# Role_Unit.net
KiCad netlist of a schematic drawn in Altium Designer
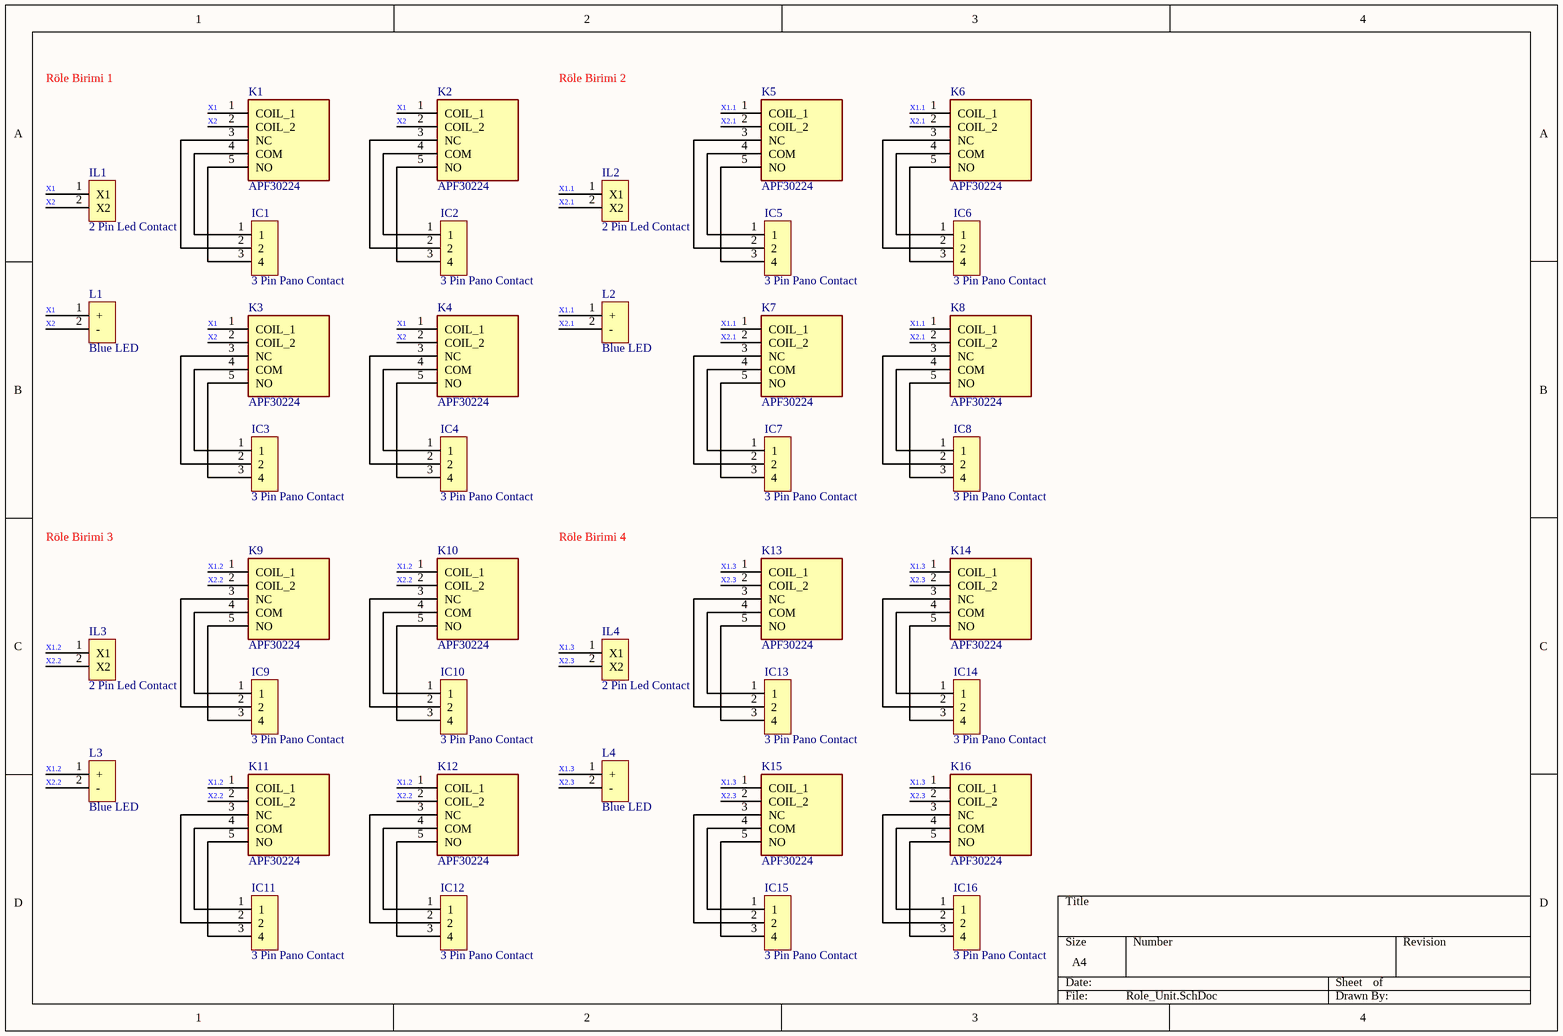
[diagram p0: Role_Unit.SchDoc]

(export (version "E")
  (design (tool "Eeschema 10.0.6"))
  (components
    (comp (ref "IC1")
      (value "3 Pin Pano Contact")
      (footprint "Contact")
      (libsource (lib "STANDART KUMANDA PANELİ") (part "Contact"))
    )
    (comp (ref "IC2")
      (value "3 Pin Pano Contact")
      (footprint "Contact")
      (libsource (lib "STANDART KUMANDA PANELİ") (part "Contact"))
    )
    (comp (ref "IC3")
      (value "3 Pin Pano Contact")
      (footprint "Contact")
      (libsource (lib "STANDART KUMANDA PANELİ") (part "Contact"))
    )
    (comp (ref "IC4")
      (value "3 Pin Pano Contact")
      (footprint "Contact")
      (libsource (lib "STANDART KUMANDA PANELİ") (part "Contact"))
    )
    (comp (ref "IC5")
      (value "3 Pin Pano Contact")
      (footprint "Contact")
      (libsource (lib "STANDART KUMANDA PANELİ") (part "Contact"))
    )
    (comp (ref "IC6")
      (value "3 Pin Pano Contact")
      (footprint "Contact")
      (libsource (lib "STANDART KUMANDA PANELİ") (part "Contact"))
    )
    (comp (ref "IC7")
      (value "3 Pin Pano Contact")
      (footprint "Contact")
      (libsource (lib "STANDART KUMANDA PANELİ") (part "Contact"))
    )
    (comp (ref "IC8")
      (value "3 Pin Pano Contact")
      (footprint "Contact")
      (libsource (lib "STANDART KUMANDA PANELİ") (part "Contact"))
    )
    (comp (ref "IC9")
      (value "3 Pin Pano Contact")
      (footprint "Contact")
      (libsource (lib "STANDART KUMANDA PANELİ") (part "Contact"))
    )
    (comp (ref "IC10")
      (value "3 Pin Pano Contact")
      (footprint "Contact")
      (libsource (lib "STANDART KUMANDA PANELİ") (part "Contact"))
    )
    (comp (ref "IC11")
      (value "3 Pin Pano Contact")
      (footprint "Contact")
      (libsource (lib "STANDART KUMANDA PANELİ") (part "Contact"))
    )
    (comp (ref "IC12")
      (value "3 Pin Pano Contact")
      (footprint "Contact")
      (libsource (lib "STANDART KUMANDA PANELİ") (part "Contact"))
    )
    (comp (ref "IC13")
      (value "3 Pin Pano Contact")
      (footprint "Contact")
      (libsource (lib "STANDART KUMANDA PANELİ") (part "Contact"))
    )
    (comp (ref "IC14")
      (value "3 Pin Pano Contact")
      (footprint "Contact")
      (libsource (lib "STANDART KUMANDA PANELİ") (part "Contact"))
    )
    (comp (ref "IC15")
      (value "3 Pin Pano Contact")
      (footprint "Contact")
      (libsource (lib "STANDART KUMANDA PANELİ") (part "Contact"))
    )
    (comp (ref "IC16")
      (value "3 Pin Pano Contact")
      (footprint "Contact")
      (libsource (lib "STANDART KUMANDA PANELİ") (part "Contact"))
    )
    (comp (ref "IL1")
      (value "2 Pin Led Contact")
      (footprint "Standart Kumanda Paneli:LED_Contact")
      (libsource (lib "STANDART KUMANDA PANELİ") (part "LED_Contact"))
    )
    (comp (ref "IL2")
      (value "2 Pin Led Contact")
      (footprint "Standart Kumanda Paneli:LED_Contact")
      (libsource (lib "STANDART KUMANDA PANELİ") (part "LED_Contact"))
    )
    (comp (ref "IL3")
      (value "2 Pin Led Contact")
      (footprint "Standart Kumanda Paneli:LED_Contact")
      (libsource (lib "STANDART KUMANDA PANELİ") (part "LED_Contact"))
    )
    (comp (ref "IL4")
      (value "2 Pin Led Contact")
      (footprint "Standart Kumanda Paneli:LED_Contact")
      (libsource (lib "STANDART KUMANDA PANELİ") (part "LED_Contact"))
    )
    (comp (ref "K1")
      (value "APF30224")
      (footprint "SamacSys:APF30224")
      (description "Relay or Contactor")
      (fields (field (name "MOUSER PART NUMBER") "769-APF30224"))
      (libsource (lib "STANDART KUMANDA PANELİ") (part "APF30224"))
    )
    (comp (ref "K2")
      (value "APF30224")
      (footprint "SamacSys:APF30224")
      (description "Relay or Contactor")
      (fields (field (name "MOUSER PART NUMBER") "769-APF30224"))
      (libsource (lib "STANDART KUMANDA PANELİ") (part "APF30224"))
    )
    (comp (ref "K3")
      (value "APF30224")
      (footprint "SamacSys:APF30224")
      (description "Relay or Contactor")
      (fields (field (name "MOUSER PART NUMBER") "769-APF30224"))
      (libsource (lib "STANDART KUMANDA PANELİ") (part "APF30224"))
    )
    (comp (ref "K4")
      (value "APF30224")
      (footprint "SamacSys:APF30224")
      (description "Relay or Contactor")
      (fields (field (name "MOUSER PART NUMBER") "769-APF30224"))
      (libsource (lib "STANDART KUMANDA PANELİ") (part "APF30224"))
    )
    (comp (ref "K5")
      (value "APF30224")
      (footprint "SamacSys:APF30224")
      (description "Relay or Contactor")
      (fields (field (name "MOUSER PART NUMBER") "769-APF30224"))
      (libsource (lib "STANDART KUMANDA PANELİ") (part "APF30224"))
    )
    (comp (ref "K6")
      (value "APF30224")
      (footprint "SamacSys:APF30224")
      (description "Relay or Contactor")
      (fields (field (name "MOUSER PART NUMBER") "769-APF30224"))
      (libsource (lib "STANDART KUMANDA PANELİ") (part "APF30224"))
    )
    (comp (ref "K7")
      (value "APF30224")
      (footprint "SamacSys:APF30224")
      (description "Relay or Contactor")
      (fields (field (name "MOUSER PART NUMBER") "769-APF30224"))
      (libsource (lib "STANDART KUMANDA PANELİ") (part "APF30224"))
    )
    (comp (ref "K8")
      (value "APF30224")
      (footprint "SamacSys:APF30224")
      (description "Relay or Contactor")
      (fields (field (name "MOUSER PART NUMBER") "769-APF30224"))
      (libsource (lib "STANDART KUMANDA PANELİ") (part "APF30224"))
    )
    (comp (ref "K9")
      (value "APF30224")
      (footprint "SamacSys:APF30224")
      (description "Relay or Contactor")
      (fields (field (name "MOUSER PART NUMBER") "769-APF30224"))
      (libsource (lib "STANDART KUMANDA PANELİ") (part "APF30224"))
    )
    (comp (ref "K10")
      (value "APF30224")
      (footprint "SamacSys:APF30224")
      (description "Relay or Contactor")
      (fields (field (name "MOUSER PART NUMBER") "769-APF30224"))
      (libsource (lib "STANDART KUMANDA PANELİ") (part "APF30224"))
    )
    (comp (ref "K11")
      (value "APF30224")
      (footprint "SamacSys:APF30224")
      (description "Relay or Contactor")
      (fields (field (name "MOUSER PART NUMBER") "769-APF30224"))
      (libsource (lib "STANDART KUMANDA PANELİ") (part "APF30224"))
    )
    (comp (ref "K12")
      (value "APF30224")
      (footprint "SamacSys:APF30224")
      (description "Relay or Contactor")
      (fields (field (name "MOUSER PART NUMBER") "769-APF30224"))
      (libsource (lib "STANDART KUMANDA PANELİ") (part "APF30224"))
    )
    (comp (ref "K13")
      (value "APF30224")
      (footprint "SamacSys:APF30224")
      (description "Relay or Contactor")
      (fields (field (name "MOUSER PART NUMBER") "769-APF30224"))
      (libsource (lib "STANDART KUMANDA PANELİ") (part "APF30224"))
    )
    (comp (ref "K14")
      (value "APF30224")
      (footprint "SamacSys:APF30224")
      (description "Relay or Contactor")
      (fields (field (name "MOUSER PART NUMBER") "769-APF30224"))
      (libsource (lib "STANDART KUMANDA PANELİ") (part "APF30224"))
    )
    (comp (ref "K15")
      (value "APF30224")
      (footprint "SamacSys:APF30224")
      (description "Relay or Contactor")
      (fields (field (name "MOUSER PART NUMBER") "769-APF30224"))
      (libsource (lib "STANDART KUMANDA PANELİ") (part "APF30224"))
    )
    (comp (ref "K16")
      (value "APF30224")
      (footprint "SamacSys:APF30224")
      (description "Relay or Contactor")
      (fields (field (name "MOUSER PART NUMBER") "769-APF30224"))
      (libsource (lib "STANDART KUMANDA PANELİ") (part "APF30224"))
    )
    (comp (ref "L1")
      (value "Blue LED")
      (footprint "MSL_AC-DC_24V_BLUE_LED")
      (libsource (lib "STANDART KUMANDA PANELİ") (part "MSL_AC-DC_24V_BLUE_LED"))
    )
    (comp (ref "L2")
      (value "Blue LED")
      (footprint "MSL_AC-DC_24V_BLUE_LED")
      (libsource (lib "STANDART KUMANDA PANELİ") (part "MSL_AC-DC_24V_BLUE_LED"))
    )
    (comp (ref "L3")
      (value "Blue LED")
      (footprint "MSL_AC-DC_24V_BLUE_LED")
      (libsource (lib "STANDART KUMANDA PANELİ") (part "MSL_AC-DC_24V_BLUE_LED"))
    )
    (comp (ref "L4")
      (value "Blue LED")
      (footprint "MSL_AC-DC_24V_BLUE_LED")
      (libsource (lib "STANDART KUMANDA PANELİ") (part "MSL_AC-DC_24V_BLUE_LED"))
    )
  )
  (nets
    (net (code "1") (name "/X1") (class "Default")
      (node (ref "IL1") (pin "1") (pinfunction "X1_1") (pintype "passive"))
      (node (ref "K1") (pin "1") (pinfunction "COIL_1_1") (pintype "passive"))
      (node (ref "K2") (pin "1") (pinfunction "COIL_1_1") (pintype "passive"))
      (node (ref "K3") (pin "1") (pinfunction "COIL_1_1") (pintype "passive"))
      (node (ref "K4") (pin "1") (pinfunction "COIL_1_1") (pintype "passive"))
      (node (ref "L1") (pin "1") (pinfunction "+_1") (pintype "passive"))
    )
    (net (code "2") (name "/X1.1") (class "Default")
      (node (ref "IL2") (pin "1") (pinfunction "X1_1") (pintype "passive"))
      (node (ref "K5") (pin "1") (pinfunction "COIL_1_1") (pintype "passive"))
      (node (ref "K6") (pin "1") (pinfunction "COIL_1_1") (pintype "passive"))
      (node (ref "K7") (pin "1") (pinfunction "COIL_1_1") (pintype "passive"))
      (node (ref "K8") (pin "1") (pinfunction "COIL_1_1") (pintype "passive"))
      (node (ref "L2") (pin "1") (pinfunction "+_1") (pintype "passive"))
    )
    (net (code "3") (name "/X1.2") (class "Default")
      (node (ref "IL3") (pin "1") (pinfunction "X1_1") (pintype "passive"))
      (node (ref "K10") (pin "1") (pinfunction "COIL_1_1") (pintype "passive"))
      (node (ref "K11") (pin "1") (pinfunction "COIL_1_1") (pintype "passive"))
      (node (ref "K12") (pin "1") (pinfunction "COIL_1_1") (pintype "passive"))
      (node (ref "K9") (pin "1") (pinfunction "COIL_1_1") (pintype "passive"))
      (node (ref "L3") (pin "1") (pinfunction "+_1") (pintype "passive"))
    )
    (net (code "4") (name "/X1.3") (class "Default")
      (node (ref "IL4") (pin "1") (pinfunction "X1_1") (pintype "passive"))
      (node (ref "K13") (pin "1") (pinfunction "COIL_1_1") (pintype "passive"))
      (node (ref "K14") (pin "1") (pinfunction "COIL_1_1") (pintype "passive"))
      (node (ref "K15") (pin "1") (pinfunction "COIL_1_1") (pintype "passive"))
      (node (ref "K16") (pin "1") (pinfunction "COIL_1_1") (pintype "passive"))
      (node (ref "L4") (pin "1") (pinfunction "+_1") (pintype "passive"))
    )
    (net (code "5") (name "/X2") (class "Default")
      (node (ref "IL1") (pin "2") (pinfunction "X2_2") (pintype "passive"))
      (node (ref "K1") (pin "2") (pinfunction "COIL_2_2") (pintype "passive"))
      (node (ref "K2") (pin "2") (pinfunction "COIL_2_2") (pintype "passive"))
      (node (ref "K3") (pin "2") (pinfunction "COIL_2_2") (pintype "passive"))
      (node (ref "K4") (pin "2") (pinfunction "COIL_2_2") (pintype "passive"))
      (node (ref "L1") (pin "2") (pinfunction "-_2") (pintype "passive"))
    )
    (net (code "6") (name "/X2.1") (class "Default")
      (node (ref "IL2") (pin "2") (pinfunction "X2_2") (pintype "passive"))
      (node (ref "K5") (pin "2") (pinfunction "COIL_2_2") (pintype "passive"))
      (node (ref "K6") (pin "2") (pinfunction "COIL_2_2") (pintype "passive"))
      (node (ref "K7") (pin "2") (pinfunction "COIL_2_2") (pintype "passive"))
      (node (ref "K8") (pin "2") (pinfunction "COIL_2_2") (pintype "passive"))
      (node (ref "L2") (pin "2") (pinfunction "-_2") (pintype "passive"))
    )
    (net (code "7") (name "/X2.2") (class "Default")
      (node (ref "IL3") (pin "2") (pinfunction "X2_2") (pintype "passive"))
      (node (ref "K10") (pin "2") (pinfunction "COIL_2_2") (pintype "passive"))
      (node (ref "K11") (pin "2") (pinfunction "COIL_2_2") (pintype "passive"))
      (node (ref "K12") (pin "2") (pinfunction "COIL_2_2") (pintype "passive"))
      (node (ref "K9") (pin "2") (pinfunction "COIL_2_2") (pintype "passive"))
      (node (ref "L3") (pin "2") (pinfunction "-_2") (pintype "passive"))
    )
    (net (code "8") (name "/X2.3") (class "Default")
      (node (ref "IL4") (pin "2") (pinfunction "X2_2") (pintype "passive"))
      (node (ref "K13") (pin "2") (pinfunction "COIL_2_2") (pintype "passive"))
      (node (ref "K14") (pin "2") (pinfunction "COIL_2_2") (pintype "passive"))
      (node (ref "K15") (pin "2") (pinfunction "COIL_2_2") (pintype "passive"))
      (node (ref "K16") (pin "2") (pinfunction "COIL_2_2") (pintype "passive"))
      (node (ref "L4") (pin "2") (pinfunction "-_2") (pintype "passive"))
    )
    (net (code "9") (name "Net-(IC1-4)") (class "Default")
      (node (ref "IC1") (pin "3") (pinfunction "4_3") (pintype "passive"))
      (node (ref "K1") (pin "5") (pinfunction "NO_5") (pintype "passive"))
    )
    (net (code "10") (name "Net-(IC2-4)") (class "Default")
      (node (ref "IC2") (pin "3") (pinfunction "4_3") (pintype "passive"))
      (node (ref "K2") (pin "5") (pinfunction "NO_5") (pintype "passive"))
    )
    (net (code "11") (name "Net-(IC3-4)") (class "Default")
      (node (ref "IC3") (pin "3") (pinfunction "4_3") (pintype "passive"))
      (node (ref "K3") (pin "5") (pinfunction "NO_5") (pintype "passive"))
    )
    (net (code "12") (name "Net-(IC4-4)") (class "Default")
      (node (ref "IC4") (pin "3") (pinfunction "4_3") (pintype "passive"))
      (node (ref "K4") (pin "5") (pinfunction "NO_5") (pintype "passive"))
    )
    (net (code "13") (name "Net-(IC5-4)") (class "Default")
      (node (ref "IC5") (pin "3") (pinfunction "4_3") (pintype "passive"))
      (node (ref "K5") (pin "5") (pinfunction "NO_5") (pintype "passive"))
    )
    (net (code "14") (name "Net-(IC6-4)") (class "Default")
      (node (ref "IC6") (pin "3") (pinfunction "4_3") (pintype "passive"))
      (node (ref "K6") (pin "5") (pinfunction "NO_5") (pintype "passive"))
    )
    (net (code "15") (name "Net-(IC7-4)") (class "Default")
      (node (ref "IC7") (pin "3") (pinfunction "4_3") (pintype "passive"))
      (node (ref "K7") (pin "5") (pinfunction "NO_5") (pintype "passive"))
    )
    (net (code "16") (name "Net-(IC8-4)") (class "Default")
      (node (ref "IC8") (pin "3") (pinfunction "4_3") (pintype "passive"))
      (node (ref "K8") (pin "5") (pinfunction "NO_5") (pintype "passive"))
    )
    (net (code "17") (name "Net-(IC9-4)") (class "Default")
      (node (ref "IC9") (pin "3") (pinfunction "4_3") (pintype "passive"))
      (node (ref "K9") (pin "5") (pinfunction "NO_5") (pintype "passive"))
    )
    (net (code "18") (name "Net-(IC10-4)") (class "Default")
      (node (ref "IC10") (pin "3") (pinfunction "4_3") (pintype "passive"))
      (node (ref "K10") (pin "5") (pinfunction "NO_5") (pintype "passive"))
    )
    (net (code "19") (name "Net-(IC11-4)") (class "Default")
      (node (ref "IC11") (pin "3") (pinfunction "4_3") (pintype "passive"))
      (node (ref "K11") (pin "5") (pinfunction "NO_5") (pintype "passive"))
    )
    (net (code "20") (name "Net-(IC12-4)") (class "Default")
      (node (ref "IC12") (pin "3") (pinfunction "4_3") (pintype "passive"))
      (node (ref "K12") (pin "5") (pinfunction "NO_5") (pintype "passive"))
    )
    (net (code "21") (name "Net-(IC13-4)") (class "Default")
      (node (ref "IC13") (pin "3") (pinfunction "4_3") (pintype "passive"))
      (node (ref "K13") (pin "5") (pinfunction "NO_5") (pintype "passive"))
    )
    (net (code "22") (name "Net-(IC14-4)") (class "Default")
      (node (ref "IC14") (pin "3") (pinfunction "4_3") (pintype "passive"))
      (node (ref "K14") (pin "5") (pinfunction "NO_5") (pintype "passive"))
    )
    (net (code "23") (name "Net-(IC15-4)") (class "Default")
      (node (ref "IC15") (pin "3") (pinfunction "4_3") (pintype "passive"))
      (node (ref "K15") (pin "5") (pinfunction "NO_5") (pintype "passive"))
    )
    (net (code "24") (name "Net-(IC16-4)") (class "Default")
      (node (ref "IC16") (pin "3") (pinfunction "4_3") (pintype "passive"))
      (node (ref "K16") (pin "5") (pinfunction "NO_5") (pintype "passive"))
    )
    (net (code "25") (name "Net-(K1-COM)") (class "Default")
      (node (ref "IC1") (pin "1") (pinfunction "1_1") (pintype "passive"))
      (node (ref "K1") (pin "4") (pinfunction "COM_4") (pintype "passive"))
    )
    (net (code "26") (name "Net-(K1-NC)") (class "Default")
      (node (ref "IC1") (pin "2") (pinfunction "2_2") (pintype "passive"))
      (node (ref "K1") (pin "3") (pinfunction "NC_3") (pintype "passive"))
    )
    (net (code "27") (name "Net-(K2-COM)") (class "Default")
      (node (ref "IC2") (pin "1") (pinfunction "1_1") (pintype "passive"))
      (node (ref "K2") (pin "4") (pinfunction "COM_4") (pintype "passive"))
    )
    (net (code "28") (name "Net-(K2-NC)") (class "Default")
      (node (ref "IC2") (pin "2") (pinfunction "2_2") (pintype "passive"))
      (node (ref "K2") (pin "3") (pinfunction "NC_3") (pintype "passive"))
    )
    (net (code "29") (name "Net-(K3-COM)") (class "Default")
      (node (ref "IC3") (pin "1") (pinfunction "1_1") (pintype "passive"))
      (node (ref "K3") (pin "4") (pinfunction "COM_4") (pintype "passive"))
    )
    (net (code "30") (name "Net-(K3-NC)") (class "Default")
      (node (ref "IC3") (pin "2") (pinfunction "2_2") (pintype "passive"))
      (node (ref "K3") (pin "3") (pinfunction "NC_3") (pintype "passive"))
    )
    (net (code "31") (name "Net-(K4-COM)") (class "Default")
      (node (ref "IC4") (pin "1") (pinfunction "1_1") (pintype "passive"))
      (node (ref "K4") (pin "4") (pinfunction "COM_4") (pintype "passive"))
    )
    (net (code "32") (name "Net-(K4-NC)") (class "Default")
      (node (ref "IC4") (pin "2") (pinfunction "2_2") (pintype "passive"))
      (node (ref "K4") (pin "3") (pinfunction "NC_3") (pintype "passive"))
    )
    (net (code "33") (name "Net-(K5-COM)") (class "Default")
      (node (ref "IC5") (pin "1") (pinfunction "1_1") (pintype "passive"))
      (node (ref "K5") (pin "4") (pinfunction "COM_4") (pintype "passive"))
    )
    (net (code "34") (name "Net-(K5-NC)") (class "Default")
      (node (ref "IC5") (pin "2") (pinfunction "2_2") (pintype "passive"))
      (node (ref "K5") (pin "3") (pinfunction "NC_3") (pintype "passive"))
    )
    (net (code "35") (name "Net-(K6-COM)") (class "Default")
      (node (ref "IC6") (pin "1") (pinfunction "1_1") (pintype "passive"))
      (node (ref "K6") (pin "4") (pinfunction "COM_4") (pintype "passive"))
    )
    (net (code "36") (name "Net-(K6-NC)") (class "Default")
      (node (ref "IC6") (pin "2") (pinfunction "2_2") (pintype "passive"))
      (node (ref "K6") (pin "3") (pinfunction "NC_3") (pintype "passive"))
    )
    (net (code "37") (name "Net-(K7-COM)") (class "Default")
      (node (ref "IC7") (pin "1") (pinfunction "1_1") (pintype "passive"))
      (node (ref "K7") (pin "4") (pinfunction "COM_4") (pintype "passive"))
    )
    (net (code "38") (name "Net-(K7-NC)") (class "Default")
      (node (ref "IC7") (pin "2") (pinfunction "2_2") (pintype "passive"))
      (node (ref "K7") (pin "3") (pinfunction "NC_3") (pintype "passive"))
    )
    (net (code "39") (name "Net-(K8-COM)") (class "Default")
      (node (ref "IC8") (pin "1") (pinfunction "1_1") (pintype "passive"))
      (node (ref "K8") (pin "4") (pinfunction "COM_4") (pintype "passive"))
    )
    (net (code "40") (name "Net-(K8-NC)") (class "Default")
      (node (ref "IC8") (pin "2") (pinfunction "2_2") (pintype "passive"))
      (node (ref "K8") (pin "3") (pinfunction "NC_3") (pintype "passive"))
    )
    (net (code "41") (name "Net-(K9-COM)") (class "Default")
      (node (ref "IC9") (pin "1") (pinfunction "1_1") (pintype "passive"))
      (node (ref "K9") (pin "4") (pinfunction "COM_4") (pintype "passive"))
    )
    (net (code "42") (name "Net-(K9-NC)") (class "Default")
      (node (ref "IC9") (pin "2") (pinfunction "2_2") (pintype "passive"))
      (node (ref "K9") (pin "3") (pinfunction "NC_3") (pintype "passive"))
    )
    (net (code "43") (name "Net-(K10-COM)") (class "Default")
      (node (ref "IC10") (pin "1") (pinfunction "1_1") (pintype "passive"))
      (node (ref "K10") (pin "4") (pinfunction "COM_4") (pintype "passive"))
    )
    (net (code "44") (name "Net-(K10-NC)") (class "Default")
      (node (ref "IC10") (pin "2") (pinfunction "2_2") (pintype "passive"))
      (node (ref "K10") (pin "3") (pinfunction "NC_3") (pintype "passive"))
    )
    (net (code "45") (name "Net-(K11-COM)") (class "Default")
      (node (ref "IC11") (pin "1") (pinfunction "1_1") (pintype "passive"))
      (node (ref "K11") (pin "4") (pinfunction "COM_4") (pintype "passive"))
    )
    (net (code "46") (name "Net-(K11-NC)") (class "Default")
      (node (ref "IC11") (pin "2") (pinfunction "2_2") (pintype "passive"))
      (node (ref "K11") (pin "3") (pinfunction "NC_3") (pintype "passive"))
    )
    (net (code "47") (name "Net-(K12-COM)") (class "Default")
      (node (ref "IC12") (pin "1") (pinfunction "1_1") (pintype "passive"))
      (node (ref "K12") (pin "4") (pinfunction "COM_4") (pintype "passive"))
    )
    (net (code "48") (name "Net-(K12-NC)") (class "Default")
      (node (ref "IC12") (pin "2") (pinfunction "2_2") (pintype "passive"))
      (node (ref "K12") (pin "3") (pinfunction "NC_3") (pintype "passive"))
    )
    (net (code "49") (name "Net-(K13-COM)") (class "Default")
      (node (ref "IC13") (pin "1") (pinfunction "1_1") (pintype "passive"))
      (node (ref "K13") (pin "4") (pinfunction "COM_4") (pintype "passive"))
    )
    (net (code "50") (name "Net-(K13-NC)") (class "Default")
      (node (ref "IC13") (pin "2") (pinfunction "2_2") (pintype "passive"))
      (node (ref "K13") (pin "3") (pinfunction "NC_3") (pintype "passive"))
    )
    (net (code "51") (name "Net-(K14-COM)") (class "Default")
      (node (ref "IC14") (pin "1") (pinfunction "1_1") (pintype "passive"))
      (node (ref "K14") (pin "4") (pinfunction "COM_4") (pintype "passive"))
    )
    (net (code "52") (name "Net-(K14-NC)") (class "Default")
      (node (ref "IC14") (pin "2") (pinfunction "2_2") (pintype "passive"))
      (node (ref "K14") (pin "3") (pinfunction "NC_3") (pintype "passive"))
    )
    (net (code "53") (name "Net-(K15-COM)") (class "Default")
      (node (ref "IC15") (pin "1") (pinfunction "1_1") (pintype "passive"))
      (node (ref "K15") (pin "4") (pinfunction "COM_4") (pintype "passive"))
    )
    (net (code "54") (name "Net-(K15-NC)") (class "Default")
      (node (ref "IC15") (pin "2") (pinfunction "2_2") (pintype "passive"))
      (node (ref "K15") (pin "3") (pinfunction "NC_3") (pintype "passive"))
    )
    (net (code "55") (name "Net-(K16-COM)") (class "Default")
      (node (ref "IC16") (pin "1") (pinfunction "1_1") (pintype "passive"))
      (node (ref "K16") (pin "4") (pinfunction "COM_4") (pintype "passive"))
    )
    (net (code "56") (name "Net-(K16-NC)") (class "Default")
      (node (ref "IC16") (pin "2") (pinfunction "2_2") (pintype "passive"))
      (node (ref "K16") (pin "3") (pinfunction "NC_3") (pintype "passive"))
    )
  )
)
